# compactron-tube-amp.net
KiCad netlist of a schematic drawn in EAGLE
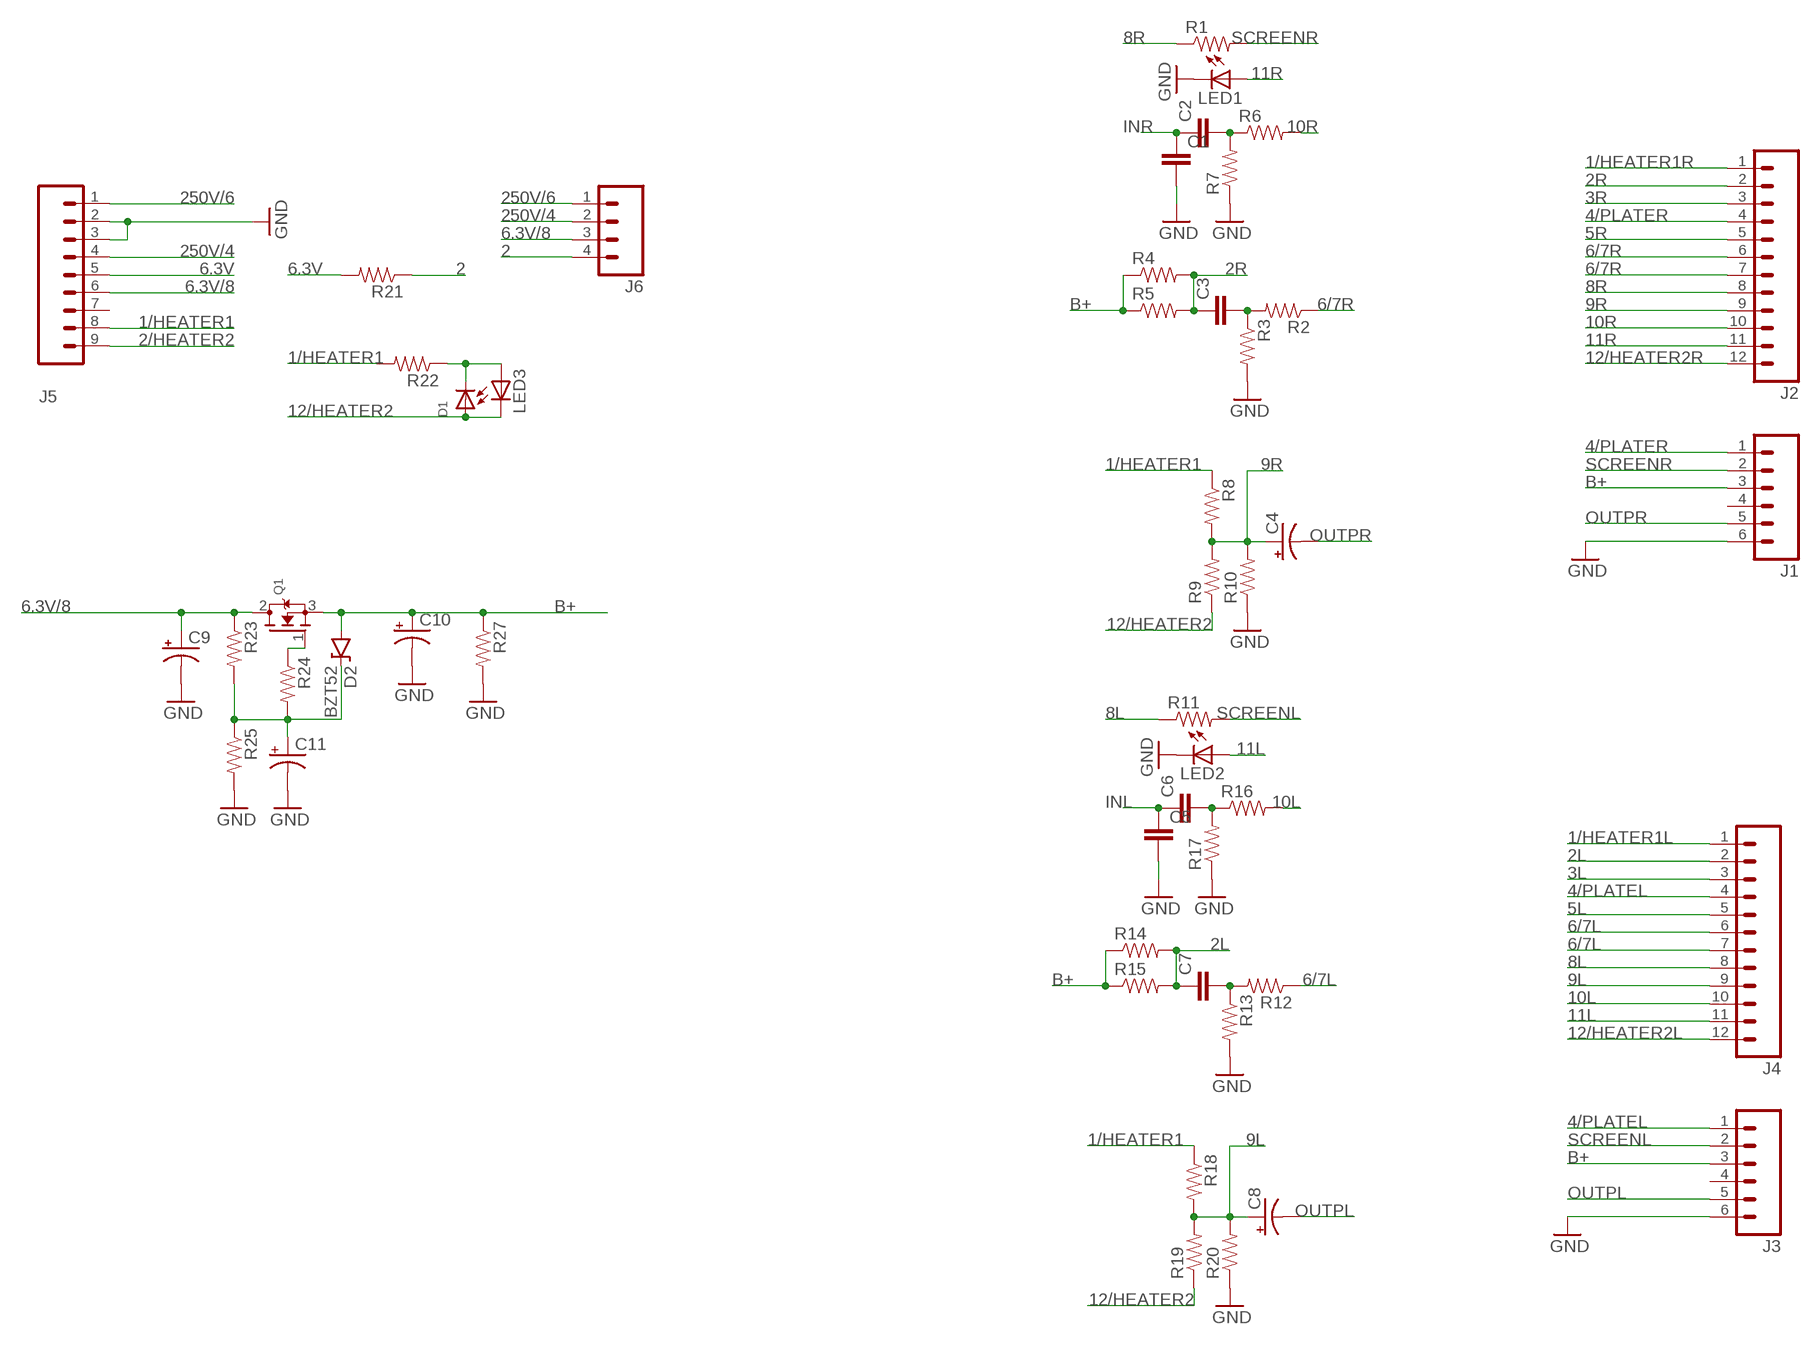
[diagram p0: schematic, sheet 1]

(export (version "E")
  (design (tool "Eeschema 10.0.6"))
  (components
    (comp (ref "C1")
      (value "C-EU275-093X316")
      (footprint "eagle-import:C275-093X316")
      (libsource (lib "eagle-import") (part "C-EU275-093X316"))
    )
    (comp (ref "C2")
      (value "C-EU275-093X316")
      (footprint "eagle-import:C275-093X316")
      (libsource (lib "eagle-import") (part "C-EU275-093X316"))
    )
    (comp (ref "C3")
      (value "C-EU275-093X316")
      (footprint "eagle-import:C275-093X316")
      (libsource (lib "eagle-import") (part "C-EU275-093X316"))
    )
    (comp (ref "C4")
      (value "CPOL-USE22-10AXIAL")
      (footprint "eagle-import:E22-10")
      (libsource (lib "eagle-import") (part "CPOL-USE22-10AXIAL"))
    )
    (comp (ref "C5")
      (value "C-EU275-093X316")
      (footprint "eagle-import:C275-093X316")
      (libsource (lib "eagle-import") (part "C-EU275-093X316"))
    )
    (comp (ref "C6")
      (value "C-EU275-093X316")
      (footprint "eagle-import:C275-093X316")
      (libsource (lib "eagle-import") (part "C-EU275-093X316"))
    )
    (comp (ref "C7")
      (value "C-EU275-093X316")
      (footprint "eagle-import:C275-093X316")
      (libsource (lib "eagle-import") (part "C-EU275-093X316"))
    )
    (comp (ref "C8")
      (value "CPOL-USE22-10AXIAL")
      (footprint "eagle-import:E22-10")
      (libsource (lib "eagle-import") (part "CPOL-USE22-10AXIAL"))
    )
    (comp (ref "C9")
      (value "CPOL-USE22-10AXIAL")
      (footprint "eagle-import:E22-10")
      (libsource (lib "eagle-import") (part "CPOL-USE22-10AXIAL"))
    )
    (comp (ref "C10")
      (value "CPOL-USE22-10AXIAL")
      (footprint "eagle-import:E22-10")
      (libsource (lib "eagle-import") (part "CPOL-USE22-10AXIAL"))
    )
    (comp (ref "C11")
      (value "CPOL-USE22-10AXIAL")
      (footprint "eagle-import:E22-10")
      (libsource (lib "eagle-import") (part "CPOL-USE22-10AXIAL"))
    )
    (comp (ref "D1")
      (value "DIODEDO-1N4148")
      (footprint "eagle-import:DO-1N4148")
      (libsource (lib "eagle-import") (part "DIODEDO-1N4148"))
    )
    (comp (ref "D2")
      (value "BZT52")
      (footprint "eagle-import:DIODE-BZT52")
      (libsource (lib "eagle-import") (part "DIODE-ZENER"))
    )
    (comp (ref "J1")
      (value "M06LONGPADS")
      (footprint "eagle-import:1X06_LONGPADS")
      (libsource (lib "eagle-import") (part "M06LONGPADS"))
    )
    (comp (ref "J2")
      (value "M12LONGPADS")
      (footprint "eagle-import:1X12_LONGPADS")
      (libsource (lib "eagle-import") (part "M12LONGPADS"))
    )
    (comp (ref "J3")
      (value "M06LONGPADS")
      (footprint "eagle-import:1X06_LONGPADS")
      (libsource (lib "eagle-import") (part "M06LONGPADS"))
    )
    (comp (ref "J4")
      (value "M12LONGPADS")
      (footprint "eagle-import:1X12_LONGPADS")
      (libsource (lib "eagle-import") (part "M12LONGPADS"))
    )
    (comp (ref "J5")
      (value "M09LONGPADS")
      (footprint "eagle-import:1X09_LONGPADS")
      (libsource (lib "eagle-import") (part "M09LONGPADS"))
    )
    (comp (ref "J6")
      (value "M04LONGPADS")
      (footprint "eagle-import:1X04_LONGPADS")
      (libsource (lib "eagle-import") (part "M04LONGPADS"))
    )
    (comp (ref "LED1")
      (value "LED5MM")
      (footprint "eagle-import:LED5MM")
      (libsource (lib "eagle-import") (part "LED5MM"))
    )
    (comp (ref "LED2")
      (value "LED5MM")
      (footprint "eagle-import:LED5MM")
      (libsource (lib "eagle-import") (part "LED5MM"))
    )
    (comp (ref "LED3")
      (value "LED5MM")
      (footprint "eagle-import:LED5MM")
      (libsource (lib "eagle-import") (part "LED5MM"))
    )
    (comp (ref "Q1")
      (value "MOSFET-NGDS_TO220V")
      (footprint "eagle-import:TO220V")
      (libsource (lib "eagle-import") (part "MOSFET-NGDS_TO220V"))
    )
    (comp (ref "R1")
      (value "RESISTORPTH-2W")
      (footprint "eagle-import:AXIAL-0.8")
      (libsource (lib "eagle-import") (part "RESISTORPTH-2W"))
    )
    (comp (ref "R2")
      (value "RESISTORPTH-2W")
      (footprint "eagle-import:AXIAL-0.8")
      (libsource (lib "eagle-import") (part "RESISTORPTH-2W"))
    )
    (comp (ref "R3")
      (value "RESISTORPTH-2W")
      (footprint "eagle-import:AXIAL-0.8")
      (libsource (lib "eagle-import") (part "RESISTORPTH-2W"))
    )
    (comp (ref "R4")
      (value "RESISTORPTH-2W")
      (footprint "eagle-import:AXIAL-0.8")
      (libsource (lib "eagle-import") (part "RESISTORPTH-2W"))
    )
    (comp (ref "R5")
      (value "RESISTORPTH-2W")
      (footprint "eagle-import:AXIAL-0.8")
      (libsource (lib "eagle-import") (part "RESISTORPTH-2W"))
    )
    (comp (ref "R6")
      (value "RESISTORPTH-2W")
      (footprint "eagle-import:AXIAL-0.8")
      (libsource (lib "eagle-import") (part "RESISTORPTH-2W"))
    )
    (comp (ref "R7")
      (value "RESISTORPTH-2W")
      (footprint "eagle-import:AXIAL-0.8")
      (libsource (lib "eagle-import") (part "RESISTORPTH-2W"))
    )
    (comp (ref "R8")
      (value "RESISTORPTH-2W")
      (footprint "eagle-import:AXIAL-0.8")
      (libsource (lib "eagle-import") (part "RESISTORPTH-2W"))
    )
    (comp (ref "R9")
      (value "RESISTORPTH-2W")
      (footprint "eagle-import:AXIAL-0.8")
      (libsource (lib "eagle-import") (part "RESISTORPTH-2W"))
    )
    (comp (ref "R10")
      (value "RESISTORPTH-2W")
      (footprint "eagle-import:AXIAL-0.8")
      (libsource (lib "eagle-import") (part "RESISTORPTH-2W"))
    )
    (comp (ref "R11")
      (value "RESISTORPTH-2W")
      (footprint "eagle-import:AXIAL-0.8")
      (libsource (lib "eagle-import") (part "RESISTORPTH-2W"))
    )
    (comp (ref "R12")
      (value "RESISTORPTH-2W")
      (footprint "eagle-import:AXIAL-0.8")
      (libsource (lib "eagle-import") (part "RESISTORPTH-2W"))
    )
    (comp (ref "R13")
      (value "RESISTORPTH-2W")
      (footprint "eagle-import:AXIAL-0.8")
      (libsource (lib "eagle-import") (part "RESISTORPTH-2W"))
    )
    (comp (ref "R14")
      (value "RESISTORPTH-2W")
      (footprint "eagle-import:AXIAL-0.8")
      (libsource (lib "eagle-import") (part "RESISTORPTH-2W"))
    )
    (comp (ref "R15")
      (value "RESISTORPTH-2W")
      (footprint "eagle-import:AXIAL-0.8")
      (libsource (lib "eagle-import") (part "RESISTORPTH-2W"))
    )
    (comp (ref "R16")
      (value "RESISTORPTH-2W")
      (footprint "eagle-import:AXIAL-0.8")
      (libsource (lib "eagle-import") (part "RESISTORPTH-2W"))
    )
    (comp (ref "R17")
      (value "RESISTORPTH-2W")
      (footprint "eagle-import:AXIAL-0.8")
      (libsource (lib "eagle-import") (part "RESISTORPTH-2W"))
    )
    (comp (ref "R18")
      (value "RESISTORPTH-2W")
      (footprint "eagle-import:AXIAL-0.8")
      (libsource (lib "eagle-import") (part "RESISTORPTH-2W"))
    )
    (comp (ref "R19")
      (value "RESISTORPTH-2W")
      (footprint "eagle-import:AXIAL-0.8")
      (libsource (lib "eagle-import") (part "RESISTORPTH-2W"))
    )
    (comp (ref "R20")
      (value "RESISTORPTH-2W")
      (footprint "eagle-import:AXIAL-0.8")
      (libsource (lib "eagle-import") (part "RESISTORPTH-2W"))
    )
    (comp (ref "R21")
      (value "RESISTORPTH-2W")
      (footprint "eagle-import:AXIAL-0.8")
      (libsource (lib "eagle-import") (part "RESISTORPTH-2W"))
    )
    (comp (ref "R22")
      (value "RESISTORPTH-2W")
      (footprint "eagle-import:AXIAL-0.8")
      (libsource (lib "eagle-import") (part "RESISTORPTH-2W"))
    )
    (comp (ref "R23")
      (value "RESISTORPTH-2W")
      (footprint "eagle-import:AXIAL-0.8")
      (libsource (lib "eagle-import") (part "RESISTORPTH-2W"))
    )
    (comp (ref "R24")
      (value "RESISTORPTH-2W")
      (footprint "eagle-import:AXIAL-0.8")
      (libsource (lib "eagle-import") (part "RESISTORPTH-2W"))
    )
    (comp (ref "R25")
      (value "RESISTORPTH-2W")
      (footprint "eagle-import:AXIAL-0.8")
      (libsource (lib "eagle-import") (part "RESISTORPTH-2W"))
    )
    (comp (ref "R27")
      (value "RESISTORPTH-2W")
      (footprint "eagle-import:AXIAL-0.8")
      (libsource (lib "eagle-import") (part "RESISTORPTH-2W"))
    )
  )
  (nets
    (net (code "1") (name "/1{slash}HEATER1") (class "Default")
      (node (ref "J5") (pin "8") (pinfunction "8_8") (pintype "passive"))
      (node (ref "R18") (pin "P$1") (pinfunction "1_P$1") (pintype "passive"))
      (node (ref "R22") (pin "P$2") (pinfunction "2_P$2") (pintype "passive"))
      (node (ref "R8") (pin "P$1") (pinfunction "1_P$1") (pintype "passive"))
    )
    (net (code "2") (name "/1{slash}HEATER1L") (class "Default")
      (node (ref "J4") (pin "1") (pinfunction "1_1") (pintype "passive"))
    )
    (net (code "3") (name "/1{slash}HEATER1R") (class "Default")
      (node (ref "J2") (pin "1") (pinfunction "1_1") (pintype "passive"))
    )
    (net (code "4") (name "/2") (class "Default")
      (node (ref "J6") (pin "4") (pinfunction "4_4") (pintype "passive"))
      (node (ref "R21") (pin "P$1") (pinfunction "1_P$1") (pintype "passive"))
    )
    (net (code "5") (name "/2L") (class "Default")
      (node (ref "C7") (pin "1") (pinfunction "1_1") (pintype "passive"))
      (node (ref "J4") (pin "2") (pinfunction "2_2") (pintype "passive"))
      (node (ref "R14") (pin "P$2") (pinfunction "2_P$2") (pintype "passive"))
      (node (ref "R15") (pin "P$2") (pinfunction "2_P$2") (pintype "passive"))
    )
    (net (code "6") (name "/2R") (class "Default")
      (node (ref "C3") (pin "1") (pinfunction "1_1") (pintype "passive"))
      (node (ref "J2") (pin "2") (pinfunction "2_2") (pintype "passive"))
      (node (ref "R4") (pin "P$2") (pinfunction "2_P$2") (pintype "passive"))
      (node (ref "R5") (pin "P$2") (pinfunction "2_P$2") (pintype "passive"))
    )
    (net (code "7") (name "/2{slash}HEATER2") (class "Default")
      (node (ref "J5") (pin "9") (pinfunction "9_9") (pintype "passive"))
    )
    (net (code "8") (name "/3L") (class "Default")
      (node (ref "J4") (pin "3") (pinfunction "3_3") (pintype "passive"))
    )
    (net (code "9") (name "/3R") (class "Default")
      (node (ref "J2") (pin "3") (pinfunction "3_3") (pintype "passive"))
    )
    (net (code "10") (name "/4{slash}PLATEL") (class "Default")
      (node (ref "J3") (pin "1") (pinfunction "1_1") (pintype "passive"))
      (node (ref "J4") (pin "4") (pinfunction "4_4") (pintype "passive"))
    )
    (net (code "11") (name "/4{slash}PLATER") (class "Default")
      (node (ref "J1") (pin "1") (pinfunction "1_1") (pintype "passive"))
      (node (ref "J2") (pin "4") (pinfunction "4_4") (pintype "passive"))
    )
    (net (code "12") (name "/5L") (class "Default")
      (node (ref "J4") (pin "5") (pinfunction "5_5") (pintype "passive"))
    )
    (net (code "13") (name "/5R") (class "Default")
      (node (ref "J2") (pin "5") (pinfunction "5_5") (pintype "passive"))
    )
    (net (code "14") (name "/6.3V") (class "Default")
      (node (ref "J5") (pin "5") (pinfunction "5_5") (pintype "passive"))
      (node (ref "R21") (pin "P$2") (pinfunction "2_P$2") (pintype "passive"))
    )
    (net (code "15") (name "/6.3V{slash}8") (class "Default")
      (node (ref "C9") (pin "+") (pinfunction "+_+") (pintype "passive"))
      (node (ref "J5") (pin "6") (pinfunction "6_6") (pintype "passive"))
      (node (ref "J6") (pin "3") (pinfunction "3_3") (pintype "passive"))
      (node (ref "Q1") (pin "2") (pinfunction "D_2") (pintype "bidirectional"))
      (node (ref "R23") (pin "P$1") (pinfunction "1_P$1") (pintype "passive"))
    )
    (net (code "16") (name "/6{slash}7L") (class "Default")
      (node (ref "J4") (pin "6") (pinfunction "6_6") (pintype "passive"))
      (node (ref "J4") (pin "7") (pinfunction "7_7") (pintype "passive"))
      (node (ref "R12") (pin "P$1") (pinfunction "1_P$1") (pintype "passive"))
    )
    (net (code "17") (name "/6{slash}7R") (class "Default")
      (node (ref "J2") (pin "6") (pinfunction "6_6") (pintype "passive"))
      (node (ref "J2") (pin "7") (pinfunction "7_7") (pintype "passive"))
      (node (ref "R2") (pin "P$1") (pinfunction "1_P$1") (pintype "passive"))
    )
    (net (code "18") (name "/8L") (class "Default")
      (node (ref "J4") (pin "8") (pinfunction "8_8") (pintype "passive"))
      (node (ref "R11") (pin "P$1") (pinfunction "1_P$1") (pintype "passive"))
    )
    (net (code "19") (name "/8R") (class "Default")
      (node (ref "J2") (pin "8") (pinfunction "8_8") (pintype "passive"))
      (node (ref "R1") (pin "P$1") (pinfunction "1_P$1") (pintype "passive"))
    )
    (net (code "20") (name "/9L") (class "Default")
      (node (ref "C8") (pin "+") (pinfunction "+_+") (pintype "passive"))
      (node (ref "J4") (pin "9") (pinfunction "9_9") (pintype "passive"))
      (node (ref "R18") (pin "P$2") (pinfunction "2_P$2") (pintype "passive"))
      (node (ref "R19") (pin "P$2") (pinfunction "2_P$2") (pintype "passive"))
      (node (ref "R20") (pin "P$2") (pinfunction "2_P$2") (pintype "passive"))
    )
    (net (code "21") (name "/9R") (class "Default")
      (node (ref "C4") (pin "+") (pinfunction "+_+") (pintype "passive"))
      (node (ref "J2") (pin "9") (pinfunction "9_9") (pintype "passive"))
      (node (ref "R10") (pin "P$2") (pinfunction "2_P$2") (pintype "passive"))
      (node (ref "R8") (pin "P$2") (pinfunction "2_P$2") (pintype "passive"))
      (node (ref "R9") (pin "P$2") (pinfunction "2_P$2") (pintype "passive"))
    )
    (net (code "22") (name "/10L") (class "Default")
      (node (ref "J4") (pin "10") (pinfunction "10_10") (pintype "passive"))
      (node (ref "R16") (pin "P$2") (pinfunction "2_P$2") (pintype "passive"))
    )
    (net (code "23") (name "/10R") (class "Default")
      (node (ref "J2") (pin "10") (pinfunction "10_10") (pintype "passive"))
      (node (ref "R6") (pin "P$2") (pinfunction "2_P$2") (pintype "passive"))
    )
    (net (code "24") (name "/11L") (class "Default")
      (node (ref "J4") (pin "11") (pinfunction "11_11") (pintype "passive"))
      (node (ref "LED2") (pin "A") (pinfunction "A_A") (pintype "passive"))
    )
    (net (code "25") (name "/11R") (class "Default")
      (node (ref "J2") (pin "11") (pinfunction "11_11") (pintype "passive"))
      (node (ref "LED1") (pin "A") (pinfunction "A_A") (pintype "passive"))
    )
    (net (code "26") (name "/12{slash}HEATER2") (class "Default")
      (node (ref "D1") (pin "A") (pinfunction "A_A") (pintype "passive"))
      (node (ref "LED3") (pin "K") (pinfunction "C_K") (pintype "passive"))
      (node (ref "R19") (pin "P$1") (pinfunction "1_P$1") (pintype "passive"))
      (node (ref "R9") (pin "P$1") (pinfunction "1_P$1") (pintype "passive"))
    )
    (net (code "27") (name "/12{slash}HEATER2L") (class "Default")
      (node (ref "J4") (pin "12") (pinfunction "12_12") (pintype "passive"))
    )
    (net (code "28") (name "/12{slash}HEATER2R") (class "Default")
      (node (ref "J2") (pin "12") (pinfunction "12_12") (pintype "passive"))
    )
    (net (code "29") (name "/250V{slash}4") (class "Default")
      (node (ref "J5") (pin "4") (pinfunction "4_4") (pintype "passive"))
      (node (ref "J6") (pin "2") (pinfunction "2_2") (pintype "passive"))
    )
    (net (code "30") (name "/250V{slash}6") (class "Default")
      (node (ref "J5") (pin "1") (pinfunction "1_1") (pintype "passive"))
      (node (ref "J6") (pin "1") (pinfunction "1_1") (pintype "passive"))
    )
    (net (code "31") (name "/B+") (class "Default")
      (node (ref "C10") (pin "+") (pinfunction "+_+") (pintype "passive"))
      (node (ref "D2") (pin "A") (pinfunction "A_A") (pintype "passive"))
      (node (ref "J1") (pin "3") (pinfunction "3_3") (pintype "passive"))
      (node (ref "J3") (pin "3") (pinfunction "3_3") (pintype "passive"))
      (node (ref "Q1") (pin "3") (pinfunction "S_3") (pintype "bidirectional"))
      (node (ref "R14") (pin "P$1") (pinfunction "1_P$1") (pintype "passive"))
      (node (ref "R15") (pin "P$1") (pinfunction "1_P$1") (pintype "passive"))
      (node (ref "R27") (pin "P$1") (pinfunction "1_P$1") (pintype "passive"))
      (node (ref "R4") (pin "P$1") (pinfunction "1_P$1") (pintype "passive"))
      (node (ref "R5") (pin "P$1") (pinfunction "1_P$1") (pintype "passive"))
    )
    (net (code "32") (name "/INL") (class "Default")
      (node (ref "C5") (pin "1") (pinfunction "1_1") (pintype "passive"))
      (node (ref "C6") (pin "1") (pinfunction "1_1") (pintype "passive"))
    )
    (net (code "33") (name "/INR") (class "Default")
      (node (ref "C1") (pin "1") (pinfunction "1_1") (pintype "passive"))
      (node (ref "C2") (pin "1") (pinfunction "1_1") (pintype "passive"))
    )
    (net (code "34") (name "/OUTPL") (class "Default")
      (node (ref "C8") (pin "-") (pinfunction "-_-") (pintype "passive"))
      (node (ref "J3") (pin "5") (pinfunction "5_5") (pintype "passive"))
    )
    (net (code "35") (name "/OUTPR") (class "Default")
      (node (ref "C4") (pin "-") (pinfunction "-_-") (pintype "passive"))
      (node (ref "J1") (pin "5") (pinfunction "5_5") (pintype "passive"))
    )
    (net (code "36") (name "/SCREENL") (class "Default")
      (node (ref "J3") (pin "2") (pinfunction "2_2") (pintype "passive"))
      (node (ref "R11") (pin "P$2") (pinfunction "2_P$2") (pintype "passive"))
    )
    (net (code "37") (name "/SCREENR") (class "Default")
      (node (ref "J1") (pin "2") (pinfunction "2_2") (pintype "passive"))
      (node (ref "R1") (pin "P$2") (pinfunction "2_P$2") (pintype "passive"))
    )
    (net (code "38") (name "GND") (class "Default")
      (node (ref "C1") (pin "2") (pinfunction "2_2") (pintype "passive"))
      (node (ref "C10") (pin "-") (pinfunction "-_-") (pintype "passive"))
      (node (ref "C11") (pin "-") (pinfunction "-_-") (pintype "passive"))
      (node (ref "C5") (pin "2") (pinfunction "2_2") (pintype "passive"))
      (node (ref "C9") (pin "-") (pinfunction "-_-") (pintype "passive"))
      (node (ref "J1") (pin "6") (pinfunction "6_6") (pintype "passive"))
      (node (ref "J3") (pin "6") (pinfunction "6_6") (pintype "passive"))
      (node (ref "J5") (pin "2") (pinfunction "2_2") (pintype "passive"))
      (node (ref "J5") (pin "3") (pinfunction "3_3") (pintype "passive"))
      (node (ref "LED1") (pin "K") (pinfunction "C_K") (pintype "passive"))
      (node (ref "LED2") (pin "K") (pinfunction "C_K") (pintype "passive"))
      (node (ref "R10") (pin "P$1") (pinfunction "1_P$1") (pintype "passive"))
      (node (ref "R13") (pin "P$2") (pinfunction "2_P$2") (pintype "passive"))
      (node (ref "R17") (pin "P$1") (pinfunction "1_P$1") (pintype "passive"))
      (node (ref "R20") (pin "P$1") (pinfunction "1_P$1") (pintype "passive"))
      (node (ref "R25") (pin "P$2") (pinfunction "2_P$2") (pintype "passive"))
      (node (ref "R27") (pin "P$2") (pinfunction "2_P$2") (pintype "passive"))
      (node (ref "R3") (pin "P$2") (pinfunction "2_P$2") (pintype "passive"))
      (node (ref "R7") (pin "P$1") (pinfunction "1_P$1") (pintype "passive"))
    )
    (net (code "39") (name "Net-(Q1-G)") (class "Default")
      (node (ref "Q1") (pin "1") (pinfunction "G_1") (pintype "bidirectional"))
      (node (ref "R24") (pin "P$1") (pinfunction "1_P$1") (pintype "passive"))
    )
    (net (code "40") (name "Net-(R2-2)") (class "Default")
      (node (ref "C3") (pin "2") (pinfunction "2_2") (pintype "passive"))
      (node (ref "R2") (pin "P$2") (pinfunction "2_P$2") (pintype "passive"))
      (node (ref "R3") (pin "P$1") (pinfunction "1_P$1") (pintype "passive"))
    )
    (net (code "41") (name "Net-(R6-1)") (class "Default")
      (node (ref "C2") (pin "2") (pinfunction "2_2") (pintype "passive"))
      (node (ref "R6") (pin "P$1") (pinfunction "1_P$1") (pintype "passive"))
      (node (ref "R7") (pin "P$2") (pinfunction "2_P$2") (pintype "passive"))
    )
    (net (code "42") (name "Net-(R12-2)") (class "Default")
      (node (ref "C7") (pin "2") (pinfunction "2_2") (pintype "passive"))
      (node (ref "R12") (pin "P$2") (pinfunction "2_P$2") (pintype "passive"))
      (node (ref "R13") (pin "P$1") (pinfunction "1_P$1") (pintype "passive"))
    )
    (net (code "43") (name "Net-(R16-1)") (class "Default")
      (node (ref "C6") (pin "2") (pinfunction "2_2") (pintype "passive"))
      (node (ref "R16") (pin "P$1") (pinfunction "1_P$1") (pintype "passive"))
      (node (ref "R17") (pin "P$2") (pinfunction "2_P$2") (pintype "passive"))
    )
    (net (code "44") (name "Net-(R22-1)") (class "Default")
      (node (ref "D1") (pin "C") (pinfunction "C_C") (pintype "passive"))
      (node (ref "LED3") (pin "A") (pinfunction "A_A") (pintype "passive"))
      (node (ref "R22") (pin "P$1") (pinfunction "1_P$1") (pintype "passive"))
    )
    (net (code "45") (name "Net-(R23-2)") (class "Default")
      (node (ref "C11") (pin "+") (pinfunction "+_+") (pintype "passive"))
      (node (ref "D2") (pin "C") (pinfunction "C_C") (pintype "passive"))
      (node (ref "R23") (pin "P$2") (pinfunction "2_P$2") (pintype "passive"))
      (node (ref "R24") (pin "P$2") (pinfunction "2_P$2") (pintype "passive"))
      (node (ref "R25") (pin "P$1") (pinfunction "1_P$1") (pintype "passive"))
    )
    (net (code "46") (name "unconnected-(J1-Pad4)") (class "Default")
      (node (ref "J1") (pin "4") (pinfunction "4_4") (pintype "passive"))
    )
    (net (code "47") (name "unconnected-(J3-Pad4)") (class "Default")
      (node (ref "J3") (pin "4") (pinfunction "4_4") (pintype "passive"))
    )
    (net (code "48") (name "unconnected-(J5-Pad7)") (class "Default")
      (node (ref "J5") (pin "7") (pinfunction "7_7") (pintype "passive"))
    )
  )
)
